# dSPLIT_fp_00.net
KiCad netlist of a schematic drawn in EAGLE
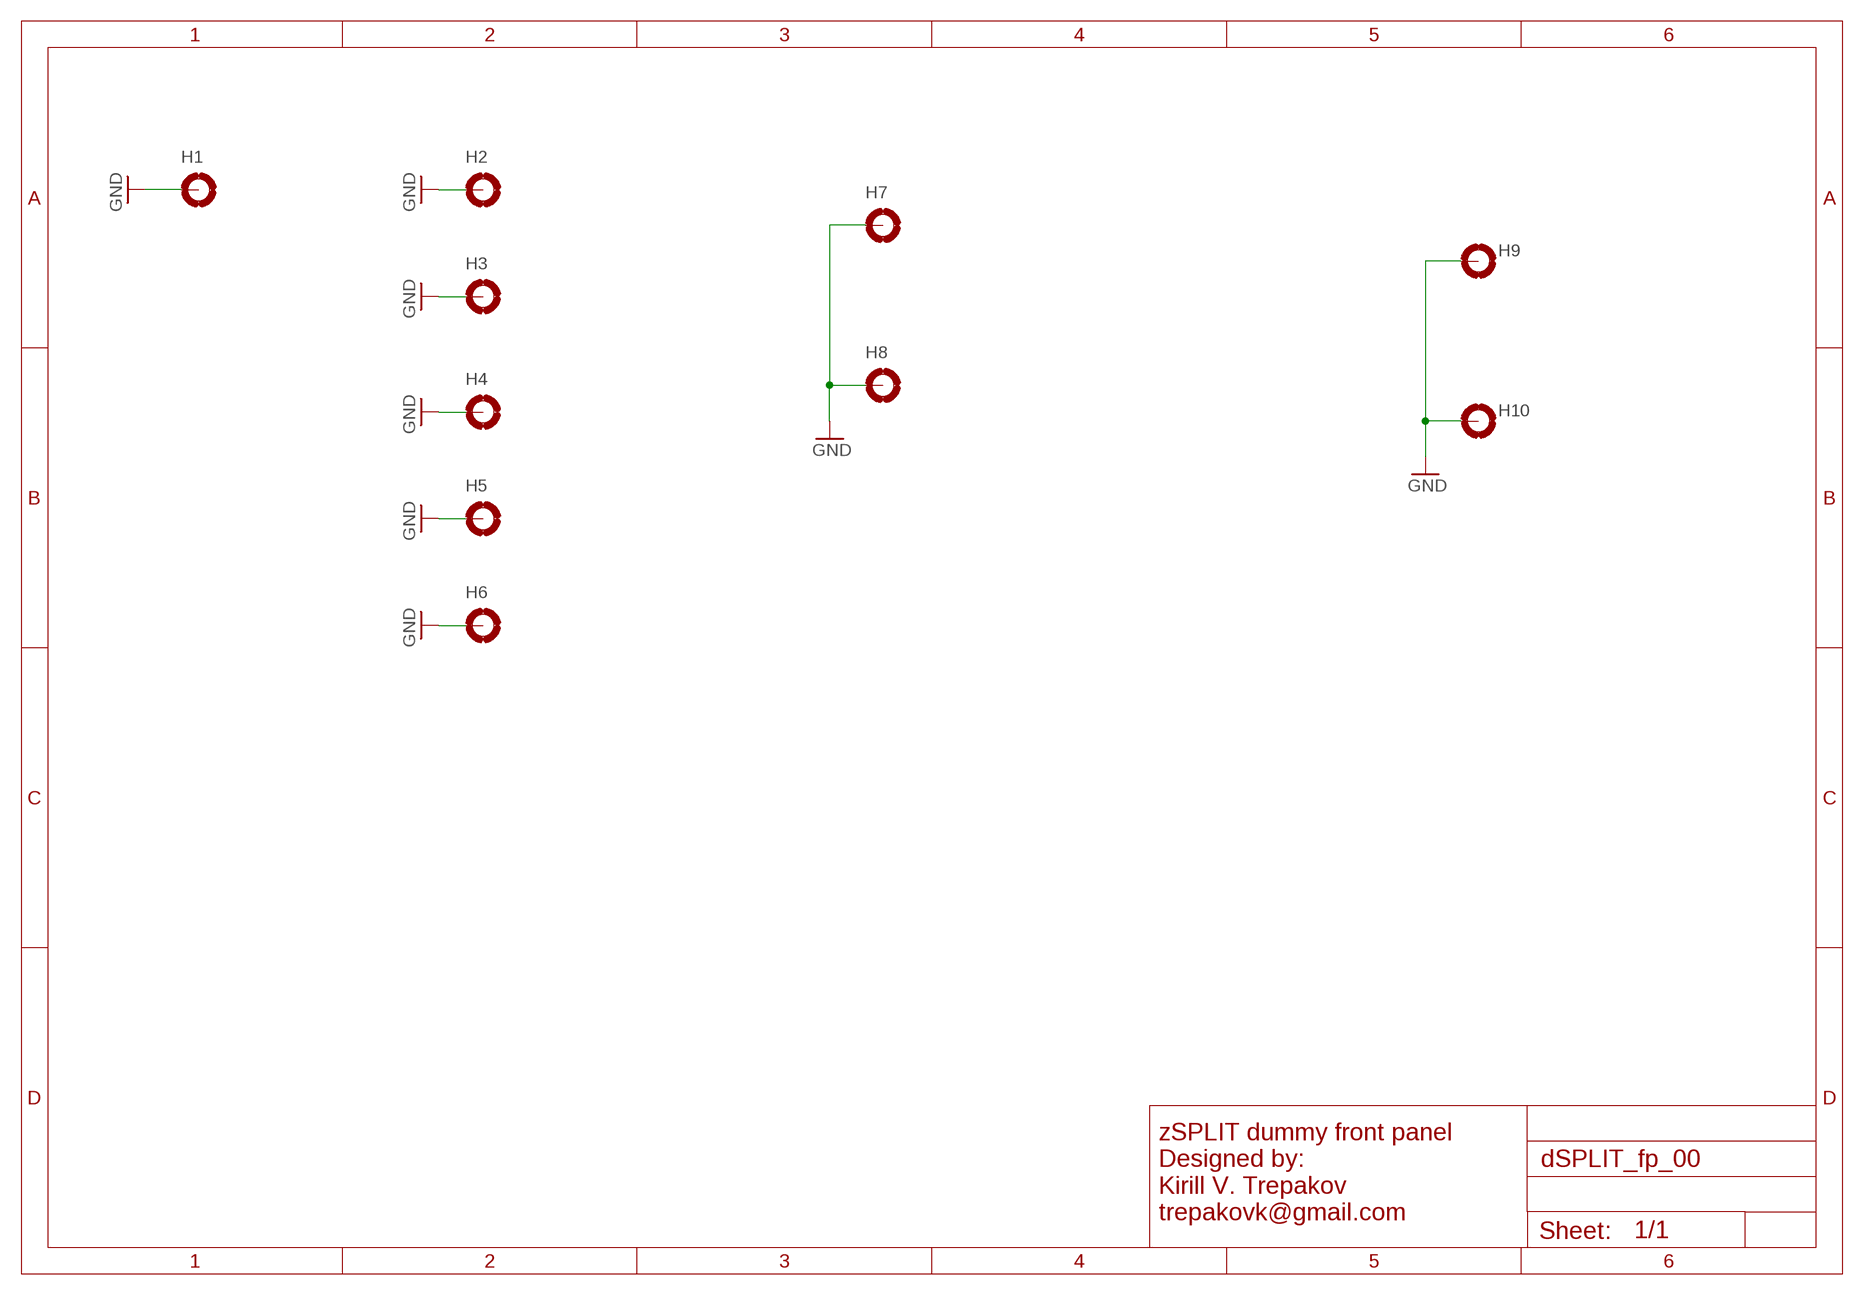
[diagram p0: schematic, sheet 1]

(export (version "E")
  (design (tool "Eeschema 10.0.6"))
  (components
    (comp (ref "H1")
      (value "MOUNT-PAD-ROUND6.223_OUT")
      (footprint "eagle-import:6.223-PAD_CLEAR")
      (libsource (lib "eagle-import") (part "MOUNT-PAD-ROUND6.223_OUT"))
    )
    (comp (ref "H2")
      (value "MOUNT-PAD-ROUND6.223_IN_1")
      (footprint "eagle-import:6.223-PAD_FILL")
      (libsource (lib "eagle-import") (part "MOUNT-PAD-ROUND6.223_IN_1"))
    )
    (comp (ref "H3")
      (value "MOUNT-PAD-ROUND6.223_IN_1")
      (footprint "eagle-import:6.223-PAD_FILL")
      (libsource (lib "eagle-import") (part "MOUNT-PAD-ROUND6.223_IN_1"))
    )
    (comp (ref "H4")
      (value "MOUNT-PAD-ROUND6.223_IN_1")
      (footprint "eagle-import:6.223-PAD_FILL")
      (libsource (lib "eagle-import") (part "MOUNT-PAD-ROUND6.223_IN_1"))
    )
    (comp (ref "H5")
      (value "MOUNT-PAD-ROUND6.223_IN_1")
      (footprint "eagle-import:6.223-PAD_FILL")
      (libsource (lib "eagle-import") (part "MOUNT-PAD-ROUND6.223_IN_1"))
    )
    (comp (ref "H6")
      (value "MOUNT-PAD-ROUND6.223_IN_1")
      (footprint "eagle-import:6.223-PAD_FILL")
      (libsource (lib "eagle-import") (part "MOUNT-PAD-ROUND6.223_IN_1"))
    )
    (comp (ref "H7")
      (value "MOUNT-PAD-ROUNDX2")
      (footprint "eagle-import:6.223-PAD_X2")
      (libsource (lib "eagle-import") (part "MOUNT-PAD-ROUNDX2"))
    )
    (comp (ref "H8")
      (value "MOUNT-PAD-ROUNDX4")
      (footprint "eagle-import:6.223-PAD_X4")
      (libsource (lib "eagle-import") (part "MOUNT-PAD-ROUNDX4"))
    )
    (comp (ref "H9")
      (value "MOUNT-PAD-LONG3.2")
      (footprint "eagle-import:3,2-PAD_L")
      (libsource (lib "eagle-import") (part "MOUNT-PAD-LONG3.2"))
    )
    (comp (ref "H10")
      (value "MOUNT-PAD-LONG3.2")
      (footprint "eagle-import:3,2-PAD_L")
      (libsource (lib "eagle-import") (part "MOUNT-PAD-LONG3.2"))
    )
  )
  (nets
    (net (code "1") (name "GND") (class "Default")
      (node (ref "H1") (pin "B6,223") (pinfunction "MOUNT_B6,223") (pintype "passive"))
      (node (ref "H10") (pin "B3,2") (pinfunction "MOUNT_B3,2") (pintype "passive"))
      (node (ref "H2") (pin "B6,223") (pinfunction "MOUNT_B6,223") (pintype "passive"))
      (node (ref "H3") (pin "B6,223") (pinfunction "MOUNT_B6,223") (pintype "passive"))
      (node (ref "H4") (pin "B6,223") (pinfunction "MOUNT_B6,223") (pintype "passive"))
      (node (ref "H5") (pin "B6,223") (pinfunction "MOUNT_B6,223") (pintype "passive"))
      (node (ref "H6") (pin "B6,223") (pinfunction "MOUNT_B6,223") (pintype "passive"))
      (node (ref "H7") (pin "B6,223") (pinfunction "MOUNT_B6,223") (pintype "passive"))
      (node (ref "H8") (pin "B6,223") (pinfunction "MOUNT_B6,223") (pintype "passive"))
      (node (ref "H9") (pin "B3,2") (pinfunction "MOUNT_B3,2") (pintype "passive"))
    )
  )
)
